# Ethernet2.net
KiCad netlist of a schematic drawn in Altium Designer
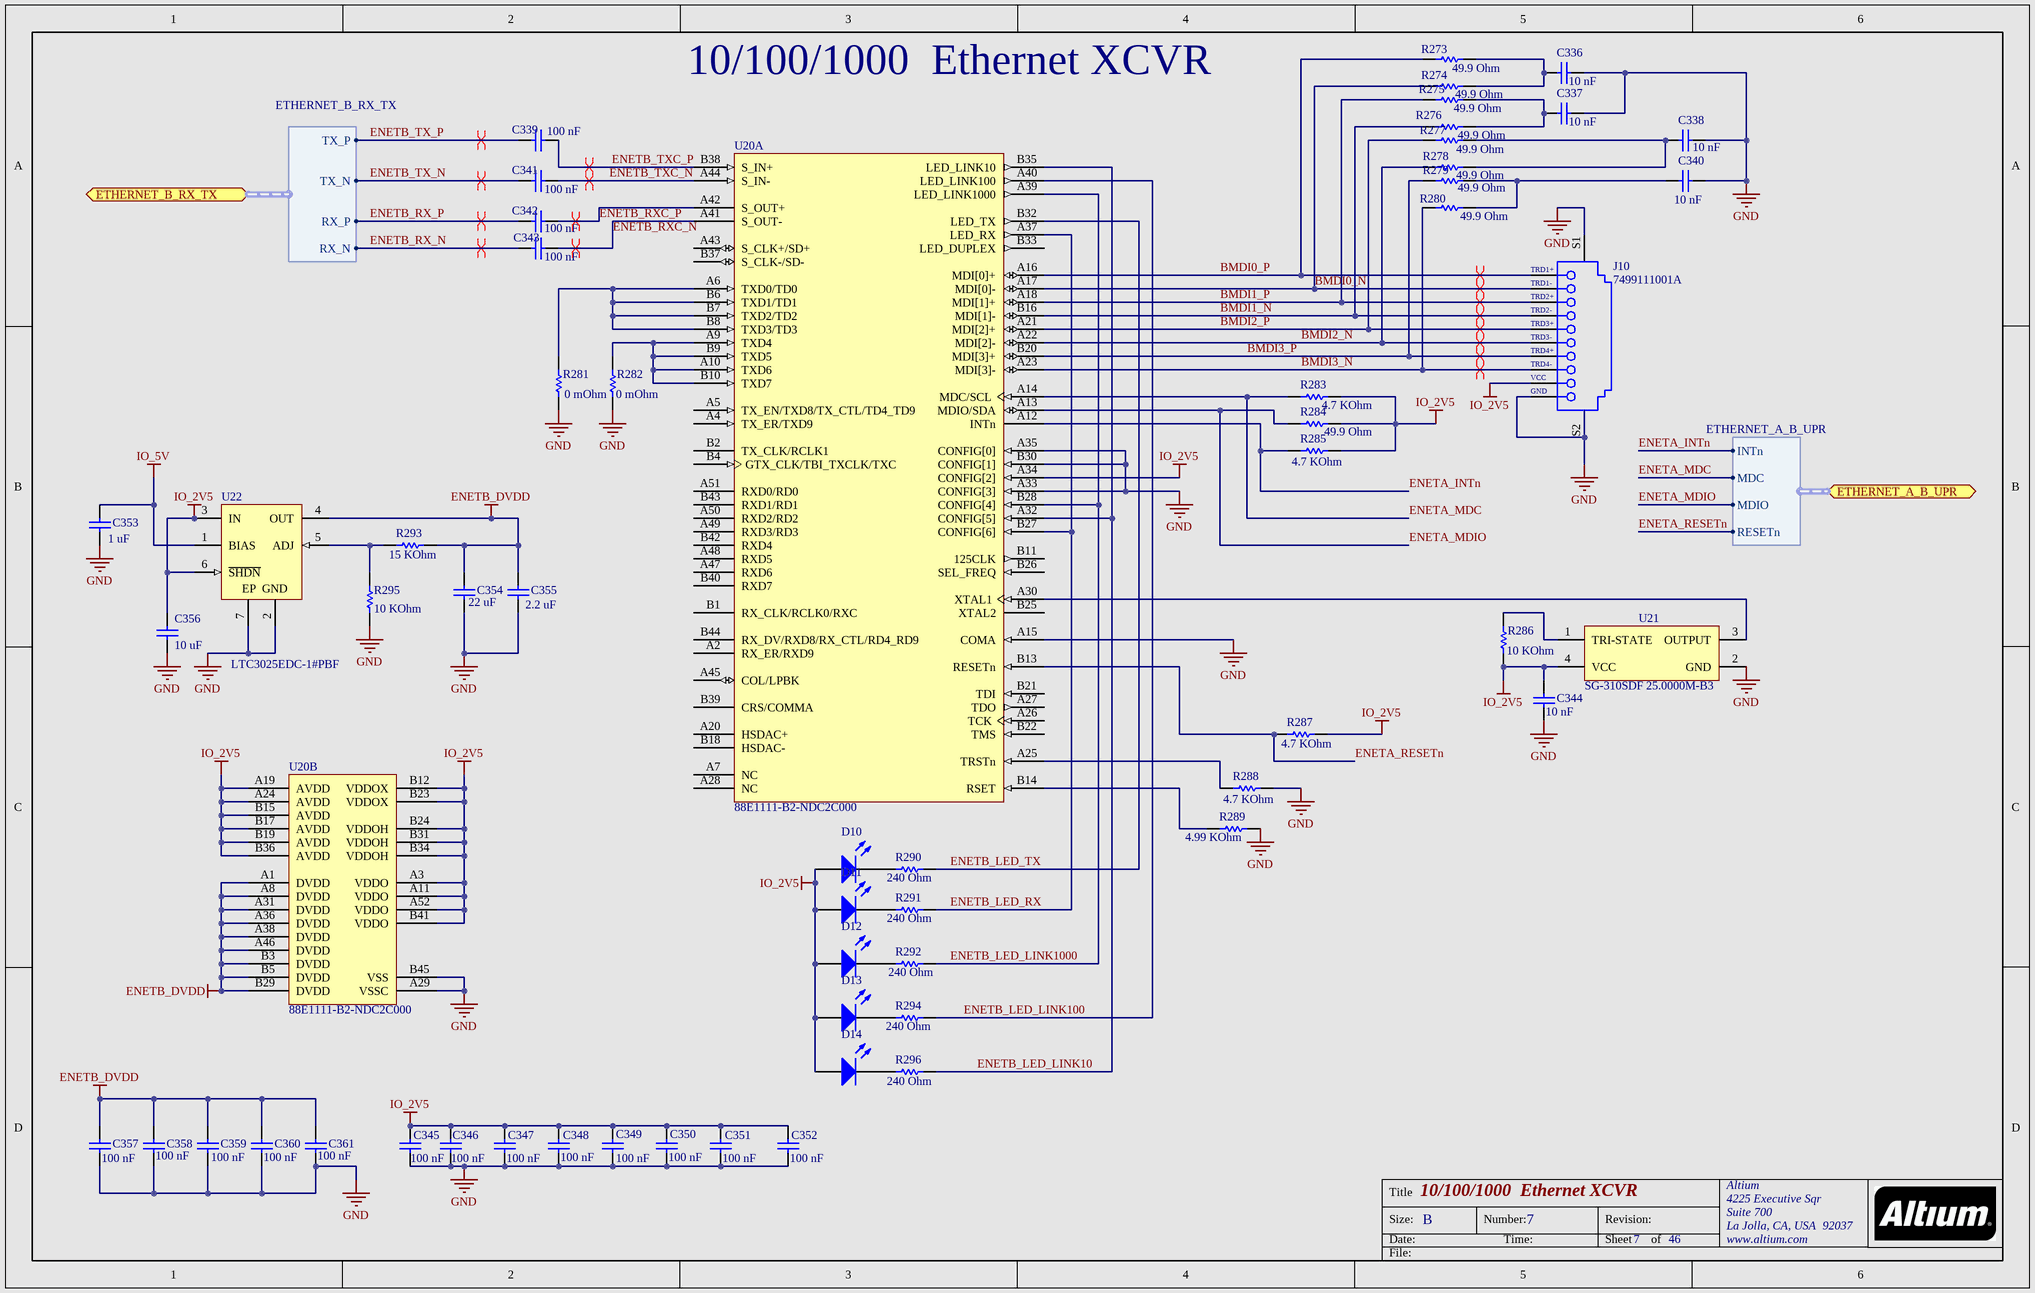
[diagram p0: Ethernet2.SchDoc]

(export (version "E")
  (design (tool "Eeschema 10.0.6"))
  (components
    (comp (ref "C336")
      (value "GRM155R71H103KA88D")
      (footprint "CAPC1005X55X25ML05T10")
      (description "Chip Capacitor, 10 nF, +/- 10%, 50 V, -55 to 125 degC, 0402 (1005 Metric), RoHS, Tape and Reel")
      (fields
        (field (name "TOLERANCE") "10%")
        (field (name "CAPACITANCE") "10 nF")
        (field (name "MANUFACTURER") "Basic Passives")
      )
      (libsource (lib "Altium Content Vault") (part "CAP-NP-2"))
    )
    (comp (ref "C337")
      (value "GRM155R71H103KA88D")
      (footprint "CAPC1005X55X25ML05T10")
      (description "Chip Capacitor, 10 nF, +/- 10%, 50 V, -55 to 125 degC, 0402 (1005 Metric), RoHS, Tape and Reel")
      (fields
        (field (name "TOLERANCE") "10%")
        (field (name "CAPACITANCE") "10 nF")
        (field (name "MANUFACTURER") "Basic Passives")
      )
      (libsource (lib "Altium Content Vault") (part "CAP-NP-2"))
    )
    (comp (ref "C338")
      (value "GRM155R71H103KA88D")
      (footprint "CAPC1005X55X25ML05T10")
      (description "Chip Capacitor, 10 nF, +/- 10%, 50 V, -55 to 125 degC, 0402 (1005 Metric), RoHS, Tape and Reel")
      (fields
        (field (name "TOLERANCE") "10%")
        (field (name "CAPACITANCE") "10 nF")
        (field (name "MANUFACTURER") "Basic Passives")
      )
      (libsource (lib "Altium Content Vault") (part "CAP-NP-2"))
    )
    (comp (ref "C339")
      (value "C1005X7R1E104M")
      (footprint "CAPC1005X55X10LL05")
      (description "Chip Capacitor, 0.1 uF, +/- 20%, 25 V, -55 to 125 degC, 0402 (1005 Metric), RoHS, Tape and Reel")
      (fields (field (name "TOLERANCE") "20%") (field (name "CAPACITANCE") "100 nF"))
      (libsource (lib "Altium Content Vault") (part "CAP-NP-2"))
    )
    (comp (ref "C340")
      (value "GRM155R71H103KA88D")
      (footprint "CAPC1005X55X25ML05T10")
      (description "Chip Capacitor, 10 nF, +/- 10%, 50 V, -55 to 125 degC, 0402 (1005 Metric), RoHS, Tape and Reel")
      (fields
        (field (name "TOLERANCE") "10%")
        (field (name "CAPACITANCE") "10 nF")
        (field (name "MANUFACTURER") "Basic Passives")
      )
      (libsource (lib "Altium Content Vault") (part "CAP-NP-2"))
    )
    (comp (ref "C341")
      (value "C1005X7R1E104M")
      (footprint "CAPC1005X55X10LL05")
      (description "Chip Capacitor, 0.1 uF, +/- 20%, 25 V, -55 to 125 degC, 0402 (1005 Metric), RoHS, Tape and Reel")
      (fields (field (name "TOLERANCE") "20%") (field (name "CAPACITANCE") "100 nF"))
      (libsource (lib "Altium Content Vault") (part "CAP-NP-2"))
    )
    (comp (ref "C342")
      (value "C1005X7R1E104M")
      (footprint "CAPC1005X55X10LL05")
      (description "Chip Capacitor, 0.1 uF, +/- 20%, 25 V, -55 to 125 degC, 0402 (1005 Metric), RoHS, Tape and Reel")
      (fields (field (name "TOLERANCE") "20%") (field (name "CAPACITANCE") "100 nF"))
      (libsource (lib "Altium Content Vault") (part "CAP-NP-2"))
    )
    (comp (ref "C343")
      (value "C1005X7R1E104M")
      (footprint "CAPC1005X55X10LL05")
      (description "Chip Capacitor, 0.1 uF, +/- 20%, 25 V, -55 to 125 degC, 0402 (1005 Metric), RoHS, Tape and Reel")
      (fields (field (name "TOLERANCE") "20%") (field (name "CAPACITANCE") "100 nF"))
      (libsource (lib "Altium Content Vault") (part "CAP-NP-2"))
    )
    (comp (ref "C344")
      (value "GRM155R71H103KA88D")
      (footprint "CAPC1005X55X25ML05T10")
      (description "Chip Capacitor, 10 nF, +/- 10%, 50 V, -55 to 125 degC, 0402 (1005 Metric), RoHS, Tape and Reel")
      (fields
        (field (name "TOLERANCE") "10%")
        (field (name "CAPACITANCE") "10 nF")
        (field (name "MANUFACTURER") "Basic Passives")
      )
      (libsource (lib "Altium Content Vault") (part "CAP-NP-2"))
    )
    (comp (ref "C345")
      (value "C1005X7R1E104M")
      (footprint "CAPC1005X55X10LL05")
      (description "Chip Capacitor, 0.1 uF, +/- 20%, 25 V, -55 to 125 degC, 0402 (1005 Metric), RoHS, Tape and Reel")
      (fields (field (name "TOLERANCE") "20%") (field (name "CAPACITANCE") "100 nF"))
      (libsource (lib "Altium Content Vault") (part "CAP-NP-2"))
    )
    (comp (ref "C346")
      (value "C1005X7R1E104M")
      (footprint "CAPC1005X55X10LL05")
      (description "Chip Capacitor, 0.1 uF, +/- 20%, 25 V, -55 to 125 degC, 0402 (1005 Metric), RoHS, Tape and Reel")
      (fields (field (name "TOLERANCE") "20%") (field (name "CAPACITANCE") "100 nF"))
      (libsource (lib "Altium Content Vault") (part "CAP-NP-2"))
    )
    (comp (ref "C347")
      (value "C1005X7R1E104M")
      (footprint "CAPC1005X55X10LL05")
      (description "Chip Capacitor, 0.1 uF, +/- 20%, 25 V, -55 to 125 degC, 0402 (1005 Metric), RoHS, Tape and Reel")
      (fields (field (name "TOLERANCE") "20%") (field (name "CAPACITANCE") "100 nF"))
      (libsource (lib "Altium Content Vault") (part "CAP-NP-2"))
    )
    (comp (ref "C348")
      (value "C1005X7R1E104M")
      (footprint "CAPC1005X55X10LL05")
      (description "Chip Capacitor, 0.1 uF, +/- 20%, 25 V, -55 to 125 degC, 0402 (1005 Metric), RoHS, Tape and Reel")
      (fields (field (name "TOLERANCE") "20%") (field (name "CAPACITANCE") "100 nF"))
      (libsource (lib "Altium Content Vault") (part "CAP-NP-2"))
    )
    (comp (ref "C349")
      (value "C1005X7R1E104M")
      (footprint "CAPC1005X55X10LL05")
      (description "Chip Capacitor, 0.1 uF, +/- 20%, 25 V, -55 to 125 degC, 0402 (1005 Metric), RoHS, Tape and Reel")
      (fields (field (name "TOLERANCE") "20%") (field (name "CAPACITANCE") "100 nF"))
      (libsource (lib "Altium Content Vault") (part "CAP-NP-2"))
    )
    (comp (ref "C350")
      (value "C1005X7R1E104M")
      (footprint "CAPC1005X55X10LL05")
      (description "Chip Capacitor, 0.1 uF, +/- 20%, 25 V, -55 to 125 degC, 0402 (1005 Metric), RoHS, Tape and Reel")
      (fields (field (name "TOLERANCE") "20%") (field (name "CAPACITANCE") "100 nF"))
      (libsource (lib "Altium Content Vault") (part "CAP-NP-2"))
    )
    (comp (ref "C351")
      (value "C1005X7R1E104M")
      (footprint "CAPC1005X55X10LL05")
      (description "Chip Capacitor, 0.1 uF, +/- 20%, 25 V, -55 to 125 degC, 0402 (1005 Metric), RoHS, Tape and Reel")
      (fields (field (name "TOLERANCE") "20%") (field (name "CAPACITANCE") "100 nF"))
      (libsource (lib "Altium Content Vault") (part "CAP-NP-2"))
    )
    (comp (ref "C352")
      (value "C1005X7R1E104M")
      (footprint "CAPC1005X55X10LL05")
      (description "Chip Capacitor, 0.1 uF, +/- 20%, 25 V, -55 to 125 degC, 0402 (1005 Metric), RoHS, Tape and Reel")
      (fields (field (name "TOLERANCE") "20%") (field (name "CAPACITANCE") "100 nF"))
      (libsource (lib "Altium Content Vault") (part "CAP-NP-2"))
    )
    (comp (ref "C353")
      (value "CGB2A1X5R1E105K033BC")
      (footprint "CAPC1005X33X10LL5")
      (description "Chip Capacitor, 1 uF, +/- 10%, 25 V, -55 to 85 degC, 0402 (1005 Metric), RoHS, Tape and Reel")
      (fields (field (name "CAPACITANCE") "1 uF") (field (name "TOLERANCE") "10%"))
      (libsource (lib "") (part "CAP-NP-2_1"))
    )
    (comp (ref "C354")
      (value "GRM31CR61E226KE15L")
      (footprint "CAPC3216X180X55ML20T25")
      (description "Chip Capacitor, 22 uF, +/- 10%, 25 V, -55 to 85 degC, 1206 (3216 Metric), RoHS, Tape and Reel")
      (fields (field (name "TOLERANCE") "10%") (field (name "CAPACITANCE") "22 uF"))
      (libsource (lib "Altium Content Vault") (part "CAP-NP-2"))
    )
    (comp (ref "C355")
      (value "GRM188R61A225KE34x")
      (footprint "CAPC1608X90X35ML10T15")
      (description "Chip Capacitor, 2.2 uF, +/- 10%, 10 V, -55 to 85 degC, 0603 (1608 Metric), RoHS, Tape and Reel")
      (fields (field (name "TOLERANCE") "10%") (field (name "CAPACITANCE") "2.2 uF"))
      (libsource (lib "") (part "CAP-NP-2_1"))
    )
    (comp (ref "C356")
      (value "C2012X5R1C106K085AC")
      (footprint "CAPC2013X100X20NL20")
      (description "Chip Capacitor, 10 uF, +/- 10%, 16 V, -55 to 85 degC, 0805 (2012 Metric), RoHS, Tape and Reel")
      (fields (field (name "TOLERANCE") "10%") (field (name "CAPACITANCE") "10 uF"))
      (libsource (lib "") (part "CAP-NP-2_1"))
    )
    (comp (ref "C357")
      (value "C1005X7R1E104M")
      (footprint "CAPC1005X55X10LL05")
      (description "Chip Capacitor, 0.1 uF, +/- 20%, 25 V, -55 to 125 degC, 0402 (1005 Metric), RoHS, Tape and Reel")
      (fields (field (name "TOLERANCE") "20%") (field (name "CAPACITANCE") "100 nF"))
      (libsource (lib "Altium Content Vault") (part "CAP-NP-2"))
    )
    (comp (ref "C358")
      (value "C1005X7R1E104M")
      (footprint "CAPC1005X55X10LL05")
      (description "Chip Capacitor, 0.1 uF, +/- 20%, 25 V, -55 to 125 degC, 0402 (1005 Metric), RoHS, Tape and Reel")
      (fields (field (name "TOLERANCE") "20%") (field (name "CAPACITANCE") "100 nF"))
      (libsource (lib "Altium Content Vault") (part "CAP-NP-2"))
    )
    (comp (ref "C359")
      (value "C1005X7R1E104M")
      (footprint "CAPC1005X55X10LL05")
      (description "Chip Capacitor, 0.1 uF, +/- 20%, 25 V, -55 to 125 degC, 0402 (1005 Metric), RoHS, Tape and Reel")
      (fields (field (name "TOLERANCE") "20%") (field (name "CAPACITANCE") "100 nF"))
      (libsource (lib "Altium Content Vault") (part "CAP-NP-2"))
    )
    (comp (ref "C360")
      (value "C1005X7R1E104M")
      (footprint "CAPC1005X55X10LL05")
      (description "Chip Capacitor, 0.1 uF, +/- 20%, 25 V, -55 to 125 degC, 0402 (1005 Metric), RoHS, Tape and Reel")
      (fields (field (name "TOLERANCE") "20%") (field (name "CAPACITANCE") "100 nF"))
      (libsource (lib "Altium Content Vault") (part "CAP-NP-2"))
    )
    (comp (ref "C361")
      (value "C1005X7R1E104M")
      (footprint "CAPC1005X55X10LL05")
      (description "Chip Capacitor, 0.1 uF, +/- 20%, 25 V, -55 to 125 degC, 0402 (1005 Metric), RoHS, Tape and Reel")
      (fields (field (name "TOLERANCE") "20%") (field (name "CAPACITANCE") "100 nF"))
      (libsource (lib "Altium Content Vault") (part "CAP-NP-2"))
    )
    (comp (ref "D10")
      (value "150060VS75000")
      (footprint "0603_A")
      (description "SMD mono-color Chip LED, WL-SMCW, Bright Green")
      (fields (field (name "MANUFACTURER") "Wuerth Elektronik"))
      (libsource (lib "Altium Content Vault") (part "CMP-1426-00006-1"))
    )
    (comp (ref "D11")
      (value "150060VS75000")
      (footprint "0603_A")
      (description "SMD mono-color Chip LED, WL-SMCW, Bright Green")
      (fields (field (name "MANUFACTURER") "Wuerth Elektronik"))
      (libsource (lib "Altium Content Vault") (part "CMP-1426-00006-1"))
    )
    (comp (ref "D12")
      (value "150060VS75000")
      (footprint "0603_A")
      (description "SMD mono-color Chip LED, WL-SMCW, Bright Green")
      (fields (field (name "MANUFACTURER") "Wuerth Elektronik"))
      (libsource (lib "Altium Content Vault") (part "CMP-1426-00006-1"))
    )
    (comp (ref "D13")
      (value "150060VS75000")
      (footprint "0603_A")
      (description "SMD mono-color Chip LED, WL-SMCW, Bright Green")
      (fields (field (name "MANUFACTURER") "Wuerth Elektronik"))
      (libsource (lib "Altium Content Vault") (part "CMP-1426-00006-1"))
    )
    (comp (ref "D14")
      (value "150060VS75000")
      (footprint "0603_A")
      (description "SMD mono-color Chip LED, WL-SMCW, Bright Green")
      (fields (field (name "MANUFACTURER") "Wuerth Elektronik"))
      (libsource (lib "Altium Content Vault") (part "CMP-1426-00006-1"))
    )
    (comp (ref "J10")
      (value "7499111001A")
      (footprint "WE-7499111001A_V")
      (description "RJ45 LAN Transformer, Modular JACK, 0 to 70 degC, 10-Pin THD, RoHS, Tube")
      (libsource (lib "Altium Content Vault") (part "RJ45-10-2SHLD_A"))
    )
    (comp (ref "R273")
      (value "NRC04F49R9TRF")
      (footprint "RESC1005X35X25NL8T10")
      (description "Chip Resistor, 49.9 Ohm, +/- 1%, 0.06 W, -55 to 155 degC, 0402 (1005 Metric), RoHS, Tape and Reel")
      (fields (field (name "TOLERANCE") "1%") (field (name "RESISTANCE") "49.9 Ohm"))
      (libsource (lib "Altium Content Vault") (part "CMP-1599-00001-2"))
    )
    (comp (ref "R274")
      (value "NRC04F49R9TRF")
      (footprint "RESC1005X35X25NL8T10")
      (description "Chip Resistor, 49.9 Ohm, +/- 1%, 0.06 W, -55 to 155 degC, 0402 (1005 Metric), RoHS, Tape and Reel")
      (fields (field (name "TOLERANCE") "1%") (field (name "RESISTANCE") "49.9 Ohm"))
      (libsource (lib "Altium Content Vault") (part "RES-2"))
    )
    (comp (ref "R275")
      (value "NRC04F49R9TRF")
      (footprint "RESC1005X35X25NL8T10")
      (description "Chip Resistor, 49.9 Ohm, +/- 1%, 0.06 W, -55 to 155 degC, 0402 (1005 Metric), RoHS, Tape and Reel")
      (fields (field (name "TOLERANCE") "1%") (field (name "RESISTANCE") "49.9 Ohm"))
      (libsource (lib "Altium Content Vault") (part "RES-2"))
    )
    (comp (ref "R276")
      (value "NRC04F49R9TRF")
      (footprint "RESC1005X35X25NL8T10")
      (description "Chip Resistor, 49.9 Ohm, +/- 1%, 0.06 W, -55 to 155 degC, 0402 (1005 Metric), RoHS, Tape and Reel")
      (fields (field (name "TOLERANCE") "1%") (field (name "RESISTANCE") "49.9 Ohm"))
      (libsource (lib "Altium Content Vault") (part "CMP-1599-00001-2"))
    )
    (comp (ref "R277")
      (value "NRC04F49R9TRF")
      (footprint "RESC1005X35X25NL8T10")
      (description "Chip Resistor, 49.9 Ohm, +/- 1%, 0.06 W, -55 to 155 degC, 0402 (1005 Metric), RoHS, Tape and Reel")
      (fields (field (name "TOLERANCE") "1%") (field (name "RESISTANCE") "49.9 Ohm"))
      (libsource (lib "Altium Content Vault") (part "RES-2"))
    )
    (comp (ref "R278")
      (value "NRC04F49R9TRF")
      (footprint "RESC1005X35X25NL8T10")
      (description "Chip Resistor, 49.9 Ohm, +/- 1%, 0.06 W, -55 to 155 degC, 0402 (1005 Metric), RoHS, Tape and Reel")
      (fields (field (name "TOLERANCE") "1%") (field (name "RESISTANCE") "49.9 Ohm"))
      (libsource (lib "Altium Content Vault") (part "RES-2"))
    )
    (comp (ref "R279")
      (value "NRC04F49R9TRF")
      (footprint "RESC1005X35X25NL8T10")
      (description "Chip Resistor, 49.9 Ohm, +/- 1%, 0.06 W, -55 to 155 degC, 0402 (1005 Metric), RoHS, Tape and Reel")
      (fields (field (name "TOLERANCE") "1%") (field (name "RESISTANCE") "49.9 Ohm"))
      (libsource (lib "Altium Content Vault") (part "CMP-1599-00001-2"))
    )
    (comp (ref "R280")
      (value "NRC04F49R9TRF")
      (footprint "RESC1005X35X25NL8T10")
      (description "Chip Resistor, 49.9 Ohm, +/- 1%, 0.06 W, -55 to 155 degC, 0402 (1005 Metric), RoHS, Tape and Reel")
      (fields (field (name "TOLERANCE") "1%") (field (name "RESISTANCE") "49.9 Ohm"))
      (libsource (lib "Altium Content Vault") (part "RES-2"))
    )
    (comp (ref "R281")
      (value "ERJ-2GE0R00X")
      (footprint "RESC1005X40X25ML05T05")
      (description "Chip Resistor, 0 mOhm, +/- 5%, 100 mW, -55 to 155 degC, 0402 (1005 Metric), RoHS, Tape and Reel")
      (fields
        (field (name "TOLERANCE") "5%")
        (field (name "RESISTANCE") "0 mOhm")
        (field (name "MANUFACTURER") "Basic Passives")
      )
      (libsource (lib "Altium Content Vault") (part "RES-2"))
    )
    (comp (ref "R282")
      (value "ERJ-2GE0R00X")
      (footprint "RESC1005X40X25ML05T05")
      (description "Chip Resistor, 0 mOhm, +/- 5%, 100 mW, -55 to 155 degC, 0402 (1005 Metric), RoHS, Tape and Reel")
      (fields
        (field (name "TOLERANCE") "5%")
        (field (name "RESISTANCE") "0 mOhm")
        (field (name "MANUFACTURER") "Basic Passives")
      )
      (libsource (lib "Altium Content Vault") (part "RES-2"))
    )
    (comp (ref "R283")
      (value "ERJ-2RKF4701X")
      (footprint "RESC1005X40X25LL05T05")
      (description "Chip Resistor, 4.7 KOhm, +/- 1%, 0.1 W, -55 to 155 degC, 0402 (1005 Metric), RoHS, Tape and Reel")
      (fields (field (name "TOLERANCE") "1%") (field (name "RESISTANCE") "4.7 KOhm"))
      (libsource (lib "Altium Content Vault") (part "RES-2"))
    )
    (comp (ref "R284")
      (value "NRC04F49R9TRF")
      (footprint "RESC1005X35X25NL8T10")
      (description "Chip Resistor, 49.9 Ohm, +/- 1%, 0.06 W, -55 to 155 degC, 0402 (1005 Metric), RoHS, Tape and Reel")
      (fields (field (name "TOLERANCE") "1%") (field (name "RESISTANCE") "49.9 Ohm"))
      (libsource (lib "Altium Content Vault") (part "CMP-1599-00001-2"))
    )
    (comp (ref "R285")
      (value "ERJ-2RKF4701X")
      (footprint "RESC1005X40X25LL05T05")
      (description "Chip Resistor, 4.7 KOhm, +/- 1%, 0.1 W, -55 to 155 degC, 0402 (1005 Metric), RoHS, Tape and Reel")
      (fields (field (name "TOLERANCE") "1%") (field (name "RESISTANCE") "4.7 KOhm"))
      (libsource (lib "Altium Content Vault") (part "RES-2"))
    )
    (comp (ref "R286")
      (value "ERJ-2RKF1002X")
      (footprint "RESC1005X40X25NL05T05")
      (description "Chip Resistor, 10 KOhm, +/- 1%, 100 mW, -55 to 155 degC, 0402 (1005 Metric), RoHS, Tape and Reel")
      (fields
        (field (name "TOLERANCE") "1%")
        (field (name "RESISTANCE") "10 KOhm")
        (field (name "MANUFACTURER") "Basic Passives")
      )
      (libsource (lib "Altium Content Vault") (part "RES-2"))
    )
    (comp (ref "R287")
      (value "ERJ-2RKF4701X")
      (footprint "RESC1005X40X25LL05T05")
      (description "Chip Resistor, 4.7 KOhm, +/- 1%, 0.1 W, -55 to 155 degC, 0402 (1005 Metric), RoHS, Tape and Reel")
      (fields (field (name "TOLERANCE") "1%") (field (name "RESISTANCE") "4.7 KOhm"))
      (libsource (lib "Altium Content Vault") (part "RES-2"))
    )
    (comp (ref "R288")
      (value "ERJ-2RKF4701X")
      (footprint "RESC1005X40X25LL05T05")
      (description "Chip Resistor, 4.7 KOhm, +/- 1%, 0.1 W, -55 to 155 degC, 0402 (1005 Metric), RoHS, Tape and Reel")
      (fields (field (name "TOLERANCE") "1%") (field (name "RESISTANCE") "4.7 KOhm"))
      (libsource (lib "Altium Content Vault") (part "RES-2"))
    )
    (comp (ref "R289")
      (value "ERJ-2RKF4991X")
      (footprint "RESC1005X40X25NL05T05")
      (description "Chip Resistor, 4.99 KOhm, +/- 1%, 100 mW, -55 to 155 degC, 0402 (1005 Metric), RoHS, Tape and Reel")
      (fields
        (field (name "TOLERANCE") "1%")
        (field (name "RESISTANCE") "4.99 KOhm")
        (field (name "MANUFACTURER") "Basic Passives")
      )
      (libsource (lib "Altium Content Vault") (part "RES-2"))
    )
    (comp (ref "R290")
      (value "ERJ-2RKF2400X")
      (footprint "RESC1005X40X25NL05T05")
      (description "Chip Resistor, 240 Ohm, +/- 1%, 100 mW, -55 to 155 degC, 0402 (1005 Metric), RoHS, Tape and Reel")
      (fields (field (name "TOLERANCE") "1%") (field (name "RESISTANCE") "240 Ohm"))
      (libsource (lib "Altium Content Vault") (part "RES-2"))
    )
    (comp (ref "R291")
      (value "ERJ-2RKF2400X")
      (footprint "RESC1005X40X25NL05T05")
      (description "Chip Resistor, 240 Ohm, +/- 1%, 100 mW, -55 to 155 degC, 0402 (1005 Metric), RoHS, Tape and Reel")
      (fields (field (name "TOLERANCE") "1%") (field (name "RESISTANCE") "240 Ohm"))
      (libsource (lib "Altium Content Vault") (part "RES-2"))
    )
    (comp (ref "R292")
      (value "ERJ-2RKF2400X")
      (footprint "RESC1005X40X25NL05T05")
      (description "Chip Resistor, 240 Ohm, +/- 1%, 100 mW, -55 to 155 degC, 0402 (1005 Metric), RoHS, Tape and Reel")
      (fields (field (name "TOLERANCE") "1%") (field (name "RESISTANCE") "240 Ohm"))
      (libsource (lib "Altium Content Vault") (part "RES-2"))
    )
    (comp (ref "R293")
      (value "ERJ-2RKF1502X")
      (footprint "RESC1005X40X25ML05T05")
      (description "Chip Resistor, 15 KOhm, +/- 1%, 100 mW, -55 to 155 degC, 0402 (1005 Metric), RoHS, Tape and Reel")
      (fields
        (field (name "RESISTANCE") "15 KOhm")
        (field (name "TOLERANCE") "1%")
        (field (name "MANUFACTURER") "Basic Passives")
      )
      (libsource (lib "Altium Content Vault") (part "RES-2"))
    )
    (comp (ref "R294")
      (value "ERJ-2RKF2400X")
      (footprint "RESC1005X40X25NL05T05")
      (description "Chip Resistor, 240 Ohm, +/- 1%, 100 mW, -55 to 155 degC, 0402 (1005 Metric), RoHS, Tape and Reel")
      (fields (field (name "TOLERANCE") "1%") (field (name "RESISTANCE") "240 Ohm"))
      (libsource (lib "Altium Content Vault") (part "RES-2"))
    )
    (comp (ref "R295")
      (value "ERJ-2RKF1002X")
      (footprint "RESC1005X40X25NL05T05")
      (description "Chip Resistor, 10 KOhm, +/- 1%, 100 mW, -55 to 155 degC, 0402 (1005 Metric), RoHS, Tape and Reel")
      (fields
        (field (name "TOLERANCE") "1%")
        (field (name "RESISTANCE") "10 KOhm")
        (field (name "MANUFACTURER") "Basic Passives")
      )
      (libsource (lib "Altium Content Vault") (part "RES-2"))
    )
    (comp (ref "R296")
      (value "ERJ-2RKF2400X")
      (footprint "RESC1005X40X25NL05T05")
      (description "Chip Resistor, 240 Ohm, +/- 1%, 100 mW, -55 to 155 degC, 0402 (1005 Metric), RoHS, Tape and Reel")
      (fields (field (name "TOLERANCE") "1%") (field (name "RESISTANCE") "240 Ohm"))
      (libsource (lib "Altium Content Vault") (part "RES-2"))
    )
    (comp (ref "U20")
      (value "88E1111-B2-NDC2C000")
      (footprint "MARV-NDC96")
      (description "Integrated 10/100/1000 Ultra Gigabit Ethernet Transceiver, Commercial Grade, 96-Pin QFN, RoHS")
      (libsource (lib "Altium Content Vault") (part "MARV-88E1111-NDC96"))
    )
    (comp (ref "U21")
      (value "SG-310SDF 25.0000M-B3")
      (footprint "EPSON-SG-310-4_V")
      (description "Crystal Oscillator (SPXO), 2.5 V, 25 MHz, -20 to 70 degC, 4-Pin SMD, RoHS, Tape and Reel")
      (libsource (lib "Altium Content Vault") (part "XTAL-1-3-4_B"))
    )
    (comp (ref "U22")
      (value "LTC3025EDC-1#PBF")
      (footprint "LT-DC6-6_V")
      (fields (field (name "MANUFACTURER") "Linear Technology"))
      (libsource (lib "Altium Content Vault") (part "LT-LTC302-DC6-6"))
    )
  )
  (nets
    (net (code "3") (name "/BMDI0_N") (class "Default")
      (node (ref "J10") (pin "2") (pinfunction "TRD1-_2") (pintype "passive"))
      (node (ref "R274") (pin "1") (pinfunction "1_1") (pintype "passive"))
      (node (ref "U20") (pin "A17") (pinfunction "MDI[0]-_A17") (pintype "bidirectional"))
    )
    (net (code "4") (name "/BMDI0_P") (class "Default")
      (node (ref "J10") (pin "1") (pinfunction "TRD1+_1") (pintype "passive"))
      (node (ref "R273") (pin "1") (pinfunction "1_1") (pintype "passive"))
      (node (ref "U20") (pin "A16") (pinfunction "MDI[0]+_A16") (pintype "bidirectional"))
    )
    (net (code "5") (name "/BMDI1_N") (class "Default")
      (node (ref "J10") (pin "4") (pinfunction "TRD2-_4") (pintype "passive"))
      (node (ref "R276") (pin "1") (pinfunction "1_1") (pintype "passive"))
      (node (ref "U20") (pin "B16") (pinfunction "MDI[1]-_B16") (pintype "bidirectional"))
    )
    (net (code "6") (name "/BMDI1_P") (class "Default")
      (node (ref "J10") (pin "3") (pinfunction "TRD2+_3") (pintype "passive"))
      (node (ref "R275") (pin "1") (pinfunction "1_1") (pintype "passive"))
      (node (ref "U20") (pin "A18") (pinfunction "MDI[1]+_A18") (pintype "bidirectional"))
    )
    (net (code "7") (name "/BMDI2_N") (class "Default")
      (node (ref "J10") (pin "6") (pinfunction "TRD3-_6") (pintype "passive"))
      (node (ref "R278") (pin "1") (pinfunction "1_1") (pintype "passive"))
      (node (ref "U20") (pin "A22") (pinfunction "MDI[2]-_A22") (pintype "bidirectional"))
    )
    (net (code "8") (name "/BMDI2_P") (class "Default")
      (node (ref "J10") (pin "5") (pinfunction "TRD3+_5") (pintype "passive"))
      (node (ref "R277") (pin "1") (pinfunction "1_1") (pintype "passive"))
      (node (ref "U20") (pin "A21") (pinfunction "MDI[2]+_A21") (pintype "bidirectional"))
    )
    (net (code "9") (name "/BMDI3_N") (class "Default")
      (node (ref "J10") (pin "8") (pinfunction "TRD4-_8") (pintype "passive"))
      (node (ref "R280") (pin "1") (pinfunction "1_1") (pintype "passive"))
      (node (ref "U20") (pin "A23") (pinfunction "MDI[3]-_A23") (pintype "bidirectional"))
    )
    (net (code "10") (name "/BMDI3_P") (class "Default")
      (node (ref "J10") (pin "7") (pinfunction "TRD4+_7") (pintype "passive"))
      (node (ref "R279") (pin "1") (pinfunction "1_1") (pintype "passive"))
      (node (ref "U20") (pin "B20") (pinfunction "MDI[3]+_B20") (pintype "bidirectional"))
    )
    (net (code "11") (name "/ENETA_INTn") (class "Default")
      (node (ref "R285") (pin "1") (pinfunction "1_1") (pintype "passive"))
      (node (ref "U20") (pin "A12") (pinfunction "INTn_A12") (pintype "passive"))
    )
    (net (code "12") (name "/ENETA_MDC") (class "Default")
      (node (ref "R283") (pin "1") (pinfunction "1_1") (pintype "passive"))
      (node (ref "U20") (pin "A14") (pinfunction "MDC/SCL_A14") (pintype "input"))
    )
    (net (code "13") (name "/ENETA_MDIO") (class "Default")
      (node (ref "R284") (pin "1") (pinfunction "1_1") (pintype "passive"))
      (node (ref "U20") (pin "A13") (pinfunction "MDIO/SDA_A13") (pintype "bidirectional"))
    )
    (net (code "14") (name "/ENETA_RESETn") (class "Default")
      (node (ref "R287") (pin "1") (pinfunction "1_1") (pintype "passive"))
      (node (ref "U20") (pin "B13") (pinfunction "RESETn_B13") (pintype "input"))
    )
    (net (code "15") (name "/ENETB_LED_LINK10") (class "Default")
      (node (ref "R296") (pin "2") (pinfunction "2_2") (pintype "passive"))
      (node (ref "U20") (pin "A32") (pinfunction "CONFIG[5]_A32") (pintype "input"))
      (node (ref "U20") (pin "B35") (pinfunction "LED_LINK10_B35") (pintype "output"))
    )
    (net (code "16") (name "/ENETB_LED_LINK100") (class "Default")
      (node (ref "R294") (pin "2") (pinfunction "2_2") (pintype "passive"))
      (node (ref "U20") (pin "A40") (pinfunction "LED_LINK100_A40") (pintype "output"))
    )
    (net (code "17") (name "/ENETB_LED_LINK1000") (class "Default")
      (node (ref "R292") (pin "2") (pinfunction "2_2") (pintype "passive"))
      (node (ref "U20") (pin "A39") (pinfunction "LED_LINK1000_A39") (pintype "output"))
      (node (ref "U20") (pin "B28") (pinfunction "CONFIG[4]_B28") (pintype "input"))
    )
    (net (code "18") (name "/ENETB_LED_RX") (class "Default")
      (node (ref "R291") (pin "2") (pinfunction "2_2") (pintype "passive"))
      (node (ref "U20") (pin "A37") (pinfunction "LED_RX_A37") (pintype "output"))
      (node (ref "U20") (pin "B27") (pinfunction "CONFIG[6]_B27") (pintype "input"))
    )
    (net (code "19") (name "/ENETB_LED_TX") (class "Default")
      (node (ref "R290") (pin "2") (pinfunction "2_2") (pintype "passive"))
      (node (ref "U20") (pin "B32") (pinfunction "LED_TX_B32") (pintype "output"))
    )
    (net (code "20") (name "/ENETB_RXC_N") (class "Default")
      (node (ref "C343") (pin "2") (pinfunction "2_2") (pintype "passive"))
      (node (ref "U20") (pin "A41") (pinfunction "S_OUT-_A41") (pintype "tri_state"))
    )
    (net (code "21") (name "/ENETB_RXC_P") (class "Default")
      (node (ref "C342") (pin "2") (pinfunction "2_2") (pintype "passive"))
      (node (ref "U20") (pin "A42") (pinfunction "S_OUT+_A42") (pintype "tri_state"))
    )
    (net (code "22") (name "/ENETB_RX_N") (class "Default")
      (node (ref "C343") (pin "1") (pinfunction "1_1") (pintype "passive"))
    )
    (net (code "23") (name "/ENETB_RX_P") (class "Default")
      (node (ref "C342") (pin "1") (pinfunction "1_1") (pintype "passive"))
    )
    (net (code "24") (name "/ENETB_TXC_N") (class "Default")
      (node (ref "C341") (pin "2") (pinfunction "2_2") (pintype "passive"))
      (node (ref "U20") (pin "A44") (pinfunction "S_IN-_A44") (pintype "input"))
    )
    (net (code "25") (name "/ENETB_TXC_P") (class "Default")
      (node (ref "C339") (pin "2") (pinfunction "2_2") (pintype "passive"))
      (node (ref "U20") (pin "B38") (pinfunction "S_IN+_B38") (pintype "input"))
    )
    (net (code "26") (name "/ENETB_TX_N") (class "Default")
      (node (ref "C341") (pin "1") (pinfunction "1_1") (pintype "passive"))
    )
    (net (code "27") (name "/ENETB_TX_P") (class "Default")
      (node (ref "C339") (pin "1") (pinfunction "1_1") (pintype "passive"))
    )
    (net (code "30") (name "ENETB_DVDD") (class "Default")
      (node (ref "C354") (pin "2") (pinfunction "2_2") (pintype "passive"))
      (node (ref "C355") (pin "2") (pinfunction "2_2") (pintype "passive"))
      (node (ref "C357") (pin "2") (pinfunction "2_2") (pintype "passive"))
      (node (ref "C358") (pin "2") (pinfunction "2_2") (pintype "passive"))
      (node (ref "C359") (pin "2") (pinfunction "2_2") (pintype "passive"))
      (node (ref "C360") (pin "2") (pinfunction "2_2") (pintype "passive"))
      (node (ref "C361") (pin "2") (pinfunction "2_2") (pintype "passive"))
      (node (ref "R293") (pin "2") (pinfunction "2_2") (pintype "passive"))
      (node (ref "U20") (pin "A1") (pinfunction "DVDD_A1") (pintype "power_in"))
      (node (ref "U20") (pin "A31") (pinfunction "DVDD_A31") (pintype "power_in"))
      (node (ref "U20") (pin "A36") (pinfunction "DVDD_A36") (pintype "power_in"))
      (node (ref "U20") (pin "A38") (pinfunction "DVDD_A38") (pintype "power_in"))
      (node (ref "U20") (pin "A46") (pinfunction "DVDD_A46") (pintype "power_in"))
      (node (ref "U20") (pin "A8") (pinfunction "DVDD_A8") (pintype "power_in"))
      (node (ref "U20") (pin "B29") (pinfunction "DVDD_B29") (pintype "power_in"))
      (node (ref "U20") (pin "B3") (pinfunction "DVDD_B3") (pintype "power_in"))
      (node (ref "U20") (pin "B5") (pinfunction "DVDD_B5") (pintype "power_in"))
      (node (ref "U22") (pin "4") (pinfunction "OUT_4") (pintype "power_in"))
    )
    (net (code "31") (name "GND") (class "Default")
      (node (ref "C336") (pin "2") (pinfunction "2_2") (pintype "passive"))
      (node (ref "C337") (pin "2") (pinfunction "2_2") (pintype "passive"))
      (node (ref "C338") (pin "2") (pinfunction "2_2") (pintype "passive"))
      (node (ref "C340") (pin "2") (pinfunction "2_2") (pintype "passive"))
      (node (ref "C344") (pin "1") (pinfunction "1_1") (pintype "passive"))
      (node (ref "C345") (pin "1") (pinfunction "1_1") (pintype "passive"))
      (node (ref "C346") (pin "1") (pinfunction "1_1") (pintype "passive"))
      (node (ref "C347") (pin "1") (pinfunction "1_1") (pintype "passive"))
      (node (ref "C348") (pin "1") (pinfunction "1_1") (pintype "passive"))
      (node (ref "C349") (pin "1") (pinfunction "1_1") (pintype "passive"))
      (node (ref "C350") (pin "1") (pinfunction "1_1") (pintype "passive"))
      (node (ref "C351") (pin "1") (pinfunction "1_1") (pintype "passive"))
      (node (ref "C352") (pin "1") (pinfunction "1_1") (pintype "passive"))
      (node (ref "C353") (pin "1") (pinfunction "1_1") (pintype "passive"))
      (node (ref "C354") (pin "1") (pinfunction "1_1") (pintype "passive"))
      (node (ref "C355") (pin "1") (pinfunction "1_1") (pintype "passive"))
      (node (ref "C356") (pin "1") (pinfunction "1_1") (pintype "passive"))
      (node (ref "C357") (pin "1") (pinfunction "1_1") (pintype "passive"))
      (node (ref "C358") (pin "1") (pinfunction "1_1") (pintype "passive"))
      (node (ref "C359") (pin "1") (pinfunction "1_1") (pintype "passive"))
      (node (ref "C360") (pin "1") (pinfunction "1_1") (pintype "passive"))
      (node (ref "C361") (pin "1") (pinfunction "1_1") (pintype "passive"))
      (node (ref "J10") (pin "10") (pinfunction "GND_10") (pintype "power_in"))
      (node (ref "J10") (pin "S1") (pinfunction "SHLD_S1") (pintype "passive"))
      (node (ref "J10") (pin "S2") (pinfunction "SHLD_S2") (pintype "passive"))
      (node (ref "R281") (pin "1") (pinfunction "1_1") (pintype "passive"))
      (node (ref "R282") (pin "1") (pinfunction "1_1") (pintype "passive"))
      (node (ref "R288") (pin "2") (pinfunction "2_2") (pintype "passive"))
      (node (ref "R289") (pin "2") (pinfunction "2_2") (pintype "passive"))
      (node (ref "R295") (pin "1") (pinfunction "1_1") (pintype "passive"))
      (node (ref "U20") (pin "A15") (pinfunction "COMA_A15") (pintype "input"))
      (node (ref "U20") (pin "A29") (pinfunction "VSSC_A29") (pintype "power_in"))
      (node (ref "U20") (pin "A33") (pinfunction "CONFIG[3]_A33") (pintype "input"))
      (node (ref "U20") (pin "A35") (pinfunction "CONFIG[0]_A35") (pintype "input"))
      (node (ref "U20") (pin "B30") (pinfunction "CONFIG[1]_B30") (pintype "input"))
      (node (ref "U20") (pin "B45") (pinfunction "VSS_B45") (pintype "power_in"))
      (node (ref "U21") (pin "2") (pinfunction "GND_2") (pintype "power_in"))
      (node (ref "U22") (pin "2") (pinfunction "GND_2") (pintype "power_in"))
      (node (ref "U22") (pin "7") (pinfunction "EP_7") (pintype "power_in"))
    )
    (net (code "32") (name "IO_2V5") (class "Default")
      (node (ref "C344") (pin "2") (pinfunction "2_2") (pintype "passive"))
      (node (ref "C345") (pin "2") (pinfunction "2_2") (pintype "passive"))
      (node (ref "C346") (pin "2") (pinfunction "2_2") (pintype "passive"))
      (node (ref "C347") (pin "2") (pinfunction "2_2") (pintype "passive"))
      (node (ref "C348") (pin "2") (pinfunction "2_2") (pintype "passive"))
      (node (ref "C349") (pin "2") (pinfunction "2_2") (pintype "passive"))
      (node (ref "C350") (pin "2") (pinfunction "2_2") (pintype "passive"))
      (node (ref "C351") (pin "2") (pinfunction "2_2") (pintype "passive"))
      (node (ref "C352") (pin "2") (pinfunction "2_2") (pintype "passive"))
      (node (ref "C356") (pin "2") (pinfunction "2_2") (pintype "passive"))
      (node (ref "D10") (pin "2") (pinfunction "A_2") (pintype "passive"))
      (node (ref "D11") (pin "2") (pinfunction "A_2") (pintype "passive"))
      (node (ref "D12") (pin "2") (pinfunction "A_2") (pintype "passive"))
      (node (ref "D13") (pin "2") (pinfunction "A_2") (pintype "passive"))
      (node (ref "D14") (pin "2") (pinfunction "A_2") (pintype "passive"))
      (node (ref "J10") (pin "9") (pinfunction "VCC_9") (pintype "power_in"))
      (node (ref "R283") (pin "2") (pinfunction "2_2") (pintype "passive"))
      (node (ref "R284") (pin "2") (pinfunction "2_2") (pintype "passive"))
      (node (ref "R285") (pin "2") (pinfunction "2_2") (pintype "passive"))
      (node (ref "R286") (pin "1") (pinfunction "1_1") (pintype "passive"))
      (node (ref "R287") (pin "2") (pinfunction "2_2") (pintype "passive"))
      (node (ref "U20") (pin "A11") (pinfunction "VDDO_A11") (pintype "power_in"))
      (node (ref "U20") (pin "A19") (pinfunction "AVDD_A19") (pintype "power_in"))
      (node (ref "U20") (pin "A24") (pinfunction "AVDD_A24") (pintype "power_in"))
      (node (ref "U20") (pin "A3") (pinfunction "VDDO_A3") (pintype "power_in"))
      (node (ref "U20") (pin "A34") (pinfunction "CONFIG[2]_A34") (pintype "input"))
      (node (ref "U20") (pin "A52") (pinfunction "VDDO_A52") (pintype "power_in"))
      (node (ref "U20") (pin "B12") (pinfunction "VDDOX_B12") (pintype "power_in"))
      (node (ref "U20") (pin "B15") (pinfunction "AVDD_B15") (pintype "power_in"))
      (node (ref "U20") (pin "B17") (pinfunction "AVDD_B17") (pintype "power_in"))
      (node (ref "U20") (pin "B19") (pinfunction "AVDD_B19") (pintype "power_in"))
      (node (ref "U20") (pin "B23") (pinfunction "VDDOX_B23") (pintype "power_in"))
      (node (ref "U20") (pin "B24") (pinfunction "VDDOH_B24") (pintype "power_in"))
      (node (ref "U20") (pin "B31") (pinfunction "VDDOH_B31") (pintype "power_in"))
      (node (ref "U20") (pin "B34") (pinfunction "VDDOH_B34") (pintype "power_in"))
      (node (ref "U20") (pin "B36") (pinfunction "AVDD_B36") (pintype "power_in"))
      (node (ref "U20") (pin "B41") (pinfunction "VDDO_B41") (pintype "power_in"))
      (node (ref "U21") (pin "4") (pinfunction "VCC_4") (pintype "power_in"))
      (node (ref "U22") (pin "3") (pinfunction "IN_3") (pintype "power_in"))
      (node (ref "U22") (pin "6") (pinfunction "~{SHDN}_6") (pintype "input"))
    )
    (net (code "33") (name "IO_5V") (class "Default")
      (node (ref "C353") (pin "2") (pinfunction "2_2") (pintype "passive"))
      (node (ref "U22") (pin "1") (pinfunction "BIAS_1") (pintype "power_in"))
    )
    (net (code "34") (name "Net-(C336-Pad1)") (class "Default")
      (node (ref "C336") (pin "1") (pinfunction "1_1") (pintype "passive"))
      (node (ref "R273") (pin "2") (pinfunction "2_2") (pintype "passive"))
      (node (ref "R274") (pin "2") (pinfunction "2_2") (pintype "passive"))
    )
    (net (code "35") (name "Net-(C337-Pad1)") (class "Default")
      (node (ref "C337") (pin "1") (pinfunction "1_1") (pintype "passive"))
      (node (ref "R275") (pin "2") (pinfunction "2_2") (pintype "passive"))
      (node (ref "R276") (pin "2") (pinfunction "2_2") (pintype "passive"))
    )
    (net (code "36") (name "Net-(C338-Pad1)") (class "Default")
      (node (ref "C338") (pin "1") (pinfunction "1_1") (pintype "passive"))
      (node (ref "R277") (pin "2") (pinfunction "2_2") (pintype "passive"))
      (node (ref "R278") (pin "2") (pinfunction "2_2") (pintype "passive"))
    )
    (net (code "37") (name "Net-(C340-Pad1)") (class "Default")
      (node (ref "C340") (pin "1") (pinfunction "1_1") (pintype "passive"))
      (node (ref "R279") (pin "2") (pinfunction "2_2") (pintype "passive"))
      (node (ref "R280") (pin "2") (pinfunction "2_2") (pintype "passive"))
    )
    (net (code "38") (name "Net-(D10-K)") (class "Default")
      (node (ref "D10") (pin "1") (pinfunction "K_1") (pintype "passive"))
      (node (ref "R290") (pin "1") (pinfunction "1_1") (pintype "passive"))
    )
    (net (code "39") (name "Net-(D11-K)") (class "Default")
      (node (ref "D11") (pin "1") (pinfunction "K_1") (pintype "passive"))
      (node (ref "R291") (pin "1") (pinfunction "1_1") (pintype "passive"))
    )
    (net (code "40") (name "Net-(D12-K)") (class "Default")
      (node (ref "D12") (pin "1") (pinfunction "K_1") (pintype "passive"))
      (node (ref "R292") (pin "1") (pinfunction "1_1") (pintype "passive"))
    )
    (net (code "41") (name "Net-(D13-K)") (class "Default")
      (node (ref "D13") (pin "1") (pinfunction "K_1") (pintype "passive"))
      (node (ref "R294") (pin "1") (pinfunction "1_1") (pintype "passive"))
    )
    (net (code "42") (name "Net-(D14-K)") (class "Default")
      (node (ref "D14") (pin "1") (pinfunction "K_1") (pintype "passive"))
      (node (ref "R296") (pin "1") (pinfunction "1_1") (pintype "passive"))
    )
    (net (code "43") (name "Net-(U20A-RSET)") (class "Default")
      (node (ref "R289") (pin "1") (pinfunction "1_1") (pintype "passive"))
      (node (ref "U20") (pin "B14") (pinfunction "RSET_B14") (pintype "input"))
    )
    (net (code "44") (name "Net-(U20A-TRSTn)") (class "Default")
      (node (ref "R288") (pin "1") (pinfunction "1_1") (pintype "passive"))
      (node (ref "U20") (pin "A25") (pinfunction "TRSTn_A25") (pintype "input"))
    )
    (net (code "45") (name "Net-(U20A-TXD0{slash}TD0)") (class "Default")
      (node (ref "R281") (pin "2") (pinfunction "2_2") (pintype "passive"))
      (node (ref "U20") (pin "A6") (pinfunction "TXD0/TD0_A6") (pintype "input"))
      (node (ref "U20") (pin "B6") (pinfunction "TXD1/TD1_B6") (pintype "input"))
      (node (ref "U20") (pin "B7") (pinfunction "TXD2/TD2_B7") (pintype "input"))
      (node (ref "U20") (pin "B8") (pinfunction "TXD3/TD3_B8") (pintype "input"))
    )
    (net (code "46") (name "Net-(U20A-TXD4)") (class "Default")
      (node (ref "R282") (pin "2") (pinfunction "2_2") (pintype "passive"))
      (node (ref "U20") (pin "A10") (pinfunction "TXD6_A10") (pintype "input"))
      (node (ref "U20") (pin "A9") (pinfunction "TXD4_A9") (pintype "input"))
      (node (ref "U20") (pin "B10") (pinfunction "TXD7_B10") (pintype "input"))
      (node (ref "U20") (pin "B9") (pinfunction "TXD5_B9") (pintype "input"))
    )
    (net (code "47") (name "Net-(U20A-XTAL1)") (class "Default")
      (node (ref "U20") (pin "A30") (pinfunction "XTAL1_A30") (pintype "input"))
      (node (ref "U21") (pin "3") (pinfunction "OUTPUT_3") (pintype "passive"))
    )
    (net (code "48") (name "Net-(U21-TRI-STATE)") (class "Default")
      (node (ref "R286") (pin "2") (pinfunction "2_2") (pintype "passive"))
      (node (ref "U21") (pin "1") (pinfunction "TRI-STATE_1") (pintype "passive"))
    )
    (net (code "49") (name "Net-(U22-ADJ)") (class "Default")
      (node (ref "R293") (pin "1") (pinfunction "1_1") (pintype "passive"))
      (node (ref "R295") (pin "2") (pinfunction "2_2") (pintype "passive"))
      (node (ref "U22") (pin "5") (pinfunction "ADJ_5") (pintype "input"))
    )
    (net (code "50") (name "unconnected-(U20A-125CLK-PadB11)") (class "Default")
      (node (ref "U20") (pin "B11") (pinfunction "125CLK_B11") (pintype "output"))
    )
    (net (code "51") (name "unconnected-(U20A-COL{slash}LPBK-PadA45)") (class "Default")
      (node (ref "U20") (pin "A45") (pinfunction "COL/LPBK_A45") (pintype "bidirectional"))
    )
    (net (code "52") (name "unconnected-(U20A-CRS{slash}COMMA-PadB39)") (class "Default")
      (node (ref "U20") (pin "B39") (pinfunction "CRS/COMMA_B39") (pintype "tri_state"))
    )
    (net (code "53") (name "unconnected-(U20A-GTX_CLK{slash}TBI_TXCLK{slash}TXC-PadB4)") (class "Default")
      (node (ref "U20") (pin "B4") (pinfunction "GTX_CLK/TBI_TXCLK/TXC_B4") (pintype "input"))
    )
    (net (code "54") (name "unconnected-(U20A-HSDAC+-PadA20)") (class "Default")
      (node (ref "U20") (pin "A20") (pinfunction "HSDAC+_A20") (pintype "passive"))
    )
    (net (code "55") (name "unconnected-(U20A-HSDAC--PadB18)") (class "Default")
      (node (ref "U20") (pin "B18") (pinfunction "HSDAC-_B18") (pintype "passive"))
    )
    (net (code "56") (name "unconnected-(U20A-LED_DUPLEX-PadB33)") (class "Default")
      (node (ref "U20") (pin "B33") (pinfunction "LED_DUPLEX_B33") (pintype "output"))
    )
    (net (code "57") (name "unconnected-(U20A-NC-PadA7)") (class "Default")
      (node (ref "U20") (pin "A7") (pinfunction "NC_A7") (pintype "passive"))
    )
    (net (code "58") (name "unconnected-(U20A-NC-PadA28)") (class "Default")
      (node (ref "U20") (pin "A28") (pinfunction "NC_A28") (pintype "passive"))
    )
    (net (code "59") (name "unconnected-(U20A-RXD0{slash}RD0-PadA51)") (class "Default")
      (node (ref "U20") (pin "A51") (pinfunction "RXD0/RD0_A51") (pintype "tri_state"))
    )
    (net (code "60") (name "unconnected-(U20A-RXD1{slash}RD1-PadB43)") (class "Default")
      (node (ref "U20") (pin "B43") (pinfunction "RXD1/RD1_B43") (pintype "tri_state"))
    )
    (net (code "61") (name "unconnected-(U20A-RXD2{slash}RD2-PadA50)") (class "Default")
      (node (ref "U20") (pin "A50") (pinfunction "RXD2/RD2_A50") (pintype "tri_state"))
    )
    (net (code "62") (name "unconnected-(U20A-RXD3{slash}RD3-PadA49)") (class "Default")
      (node (ref "U20") (pin "A49") (pinfunction "RXD3/RD3_A49") (pintype "tri_state"))
    )
    (net (code "63") (name "unconnected-(U20A-RXD4-PadB42)") (class "Default")
      (node (ref "U20") (pin "B42") (pinfunction "RXD4_B42") (pintype "tri_state"))
    )
    (net (code "64") (name "unconnected-(U20A-RXD5-PadA48)") (class "Default")
      (node (ref "U20") (pin "A48") (pinfunction "RXD5_A48") (pintype "tri_state"))
    )
    (net (code "65") (name "unconnected-(U20A-RXD6-PadA47)") (class "Default")
      (node (ref "U20") (pin "A47") (pinfunction "RXD6_A47") (pintype "tri_state"))
    )
    (net (code "66") (name "unconnected-(U20A-RXD7-PadB40)") (class "Default")
      (node (ref "U20") (pin "B40") (pinfunction "RXD7_B40") (pintype "tri_state"))
    )
    (net (code "67") (name "unconnected-(U20A-RX_CLK{slash}RCLK0{slash}RXC-PadB1)") (class "Default")
      (node (ref "U20") (pin "B1") (pinfunction "RX_CLK/RCLK0/RXC_B1") (pintype "tri_state"))
    )
    (net (code "68") (name "unconnected-(U20A-RX_DV{slash}RXD8{slash}RX_CTL{slash}RD4_RD9-PadB44)") (class "Default")
      (node (ref "U20") (pin "B44") (pinfunction "RX_DV/RXD8/RX_CTL/RD4_RD9_B44") (pintype "tri_state"))
    )
    (net (code "69") (name "unconnected-(U20A-RX_ER{slash}RXD9-PadA2)") (class "Default")
      (node (ref "U20") (pin "A2") (pinfunction "RX_ER/RXD9_A2") (pintype "tri_state"))
    )
    (net (code "70") (name "unconnected-(U20A-SEL_FREQ-PadB26)") (class "Default")
      (node (ref "U20") (pin "B26") (pinfunction "SEL_FREQ_B26") (pintype "input"))
    )
    (net (code "71") (name "unconnected-(U20A-S_CLK+{slash}SD+-PadA43)") (class "Default")
      (node (ref "U20") (pin "A43") (pinfunction "S_CLK+/SD+_A43") (pintype "bidirectional"))
    )
    (net (code "72") (name "unconnected-(U20A-S_CLK-{slash}SD--PadB37)") (class "Default")
      (node (ref "U20") (pin "B37") (pinfunction "S_CLK-/SD-_B37") (pintype "bidirectional"))
    )
    (net (code "73") (name "unconnected-(U20A-TCK-PadA26)") (class "Default")
      (node (ref "U20") (pin "A26") (pinfunction "TCK_A26") (pintype "input"))
    )
    (net (code "74") (name "unconnected-(U20A-TDI-PadB21)") (class "Default")
      (node (ref "U20") (pin "B21") (pinfunction "TDI_B21") (pintype "input"))
    )
    (net (code "75") (name "unconnected-(U20A-TDO-PadA27)") (class "Default")
      (node (ref "U20") (pin "A27") (pinfunction "TDO_A27") (pintype "output"))
    )
    (net (code "76") (name "unconnected-(U20A-TMS-PadB22)") (class "Default")
      (node (ref "U20") (pin "B22") (pinfunction "TMS_B22") (pintype "input"))
    )
    (net (code "77") (name "unconnected-(U20A-TX_CLK{slash}RCLK1-PadB2)") (class "Default")
      (node (ref "U20") (pin "B2") (pinfunction "TX_CLK/RCLK1_B2") (pintype "tri_state"))
    )
    (net (code "78") (name "unconnected-(U20A-TX_EN{slash}TXD8{slash}TX_CTL{slash}TD4_TD9-PadA5)") (class "Default")
      (node (ref "U20") (pin "A5") (pinfunction "TX_EN/TXD8/TX_CTL/TD4_TD9_A5") (pintype "input"))
    )
    (net (code "79") (name "unconnected-(U20A-TX_ER{slash}TXD9-PadA4)") (class "Default")
      (node (ref "U20") (pin "A4") (pinfunction "TX_ER/TXD9_A4") (pintype "input"))
    )
    (net (code "80") (name "unconnected-(U20A-XTAL2-PadB25)") (class "Default")
      (node (ref "U20") (pin "B25") (pinfunction "XTAL2_B25") (pintype "passive"))
    )
  )
)
